# SerialConnector.net
KiCad netlist of a schematic drawn in Altium Designer
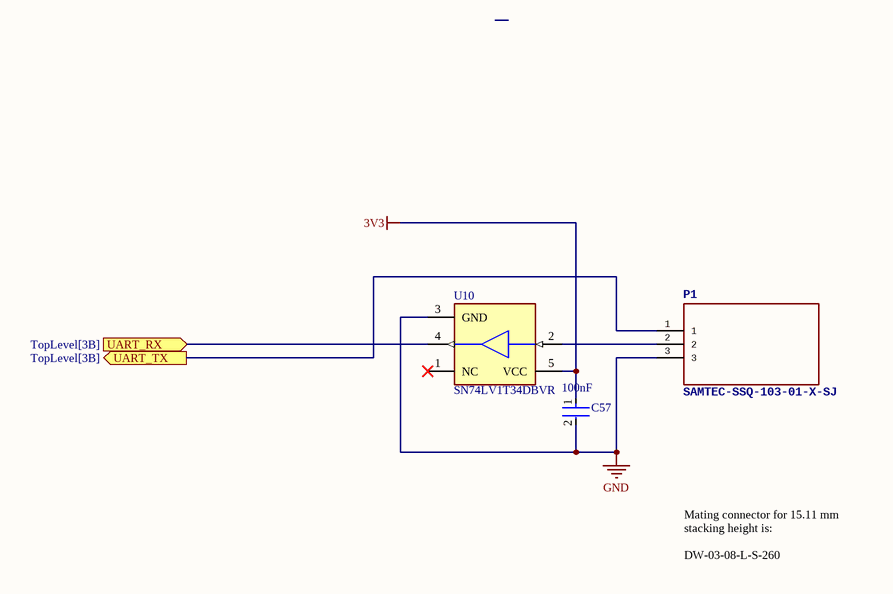
[diagram p0: SerialConnector.SchDoc]

(export (version "E")
  (design (tool "Eeschema 10.0.6"))
  (components
    (comp (ref "C57")
      (value "GRM155R71E104KE14J")
      (footprint "FP-GRM155-0_05-IPC_C")
      (description "Chip Multilayer Ceramic Capacitors for General Purpose, 0402, 0.10uF, X7R, 15%, 10%, 25V")
      (fields (field (name "CAPACITANCE") "100nF") (field (name "TOLERANCE") "10%"))
      (libsource (lib "Altium Content Vault") (part "02cd4be3c70576c341d710602a673aa"))
    )
    (comp (ref "P1")
      (value "SAMTEC-SSQ-103-01-X-SJ")
      (footprint "SAMTEC-SSQ-103-01-X-S")
      (libsource (lib "SAMTEC-SSQ-103-01-X-S") (part "SAMTEC-SSQ-103-01-X-SJ"))
    )
    (comp (ref "U10")
      (value "SN74LV1T34DBVR")
      (footprint "FP-DBV0005A-IPC_B")
      (description "IC BUF NON-INVERT 5.5V SOT23-5")
      (libsource (lib "Altium Content Vault") (part "d03805866fcc65e5014dff611fc4129"))
    )
  )
  (nets
    (net (code "1") (name "/UART_RX") (class "Default")
      (node (ref "U10") (pin "4") (pinfunction "Y_4") (pintype "output"))
    )
    (net (code "2") (name "/UART_TX") (class "Default")
      (node (ref "P1") (pin "1") (pinfunction "1_1") (pintype "passive"))
    )
    (net (code "3") (name "3V3") (class "Default")
      (node (ref "C57") (pin "1") (pinfunction "1_1") (pintype "passive"))
      (node (ref "U10") (pin "5") (pinfunction "VCC_5") (pintype "power_in"))
    )
    (net (code "4") (name "GND") (class "Default")
      (node (ref "C57") (pin "2") (pinfunction "2_2") (pintype "passive"))
      (node (ref "P1") (pin "3") (pinfunction "3_3") (pintype "passive"))
      (node (ref "U10") (pin "3") (pinfunction "GND_3") (pintype "power_in"))
    )
    (net (code "5") (name "Net-(U10-A)") (class "Default")
      (node (ref "P1") (pin "2") (pinfunction "2_2") (pintype "passive"))
      (node (ref "U10") (pin "2") (pinfunction "A_2") (pintype "input"))
    )
    (net (code "6") (name "unconnected-(U10-NC-Pad1)") (class "Default")
      (node (ref "U10") (pin "1") (pinfunction "NC_1") (pintype "passive+no_connect"))
    )
  )
)
